# Connector_Board_rev1.net
KiCad netlist of a schematic drawn in EAGLE
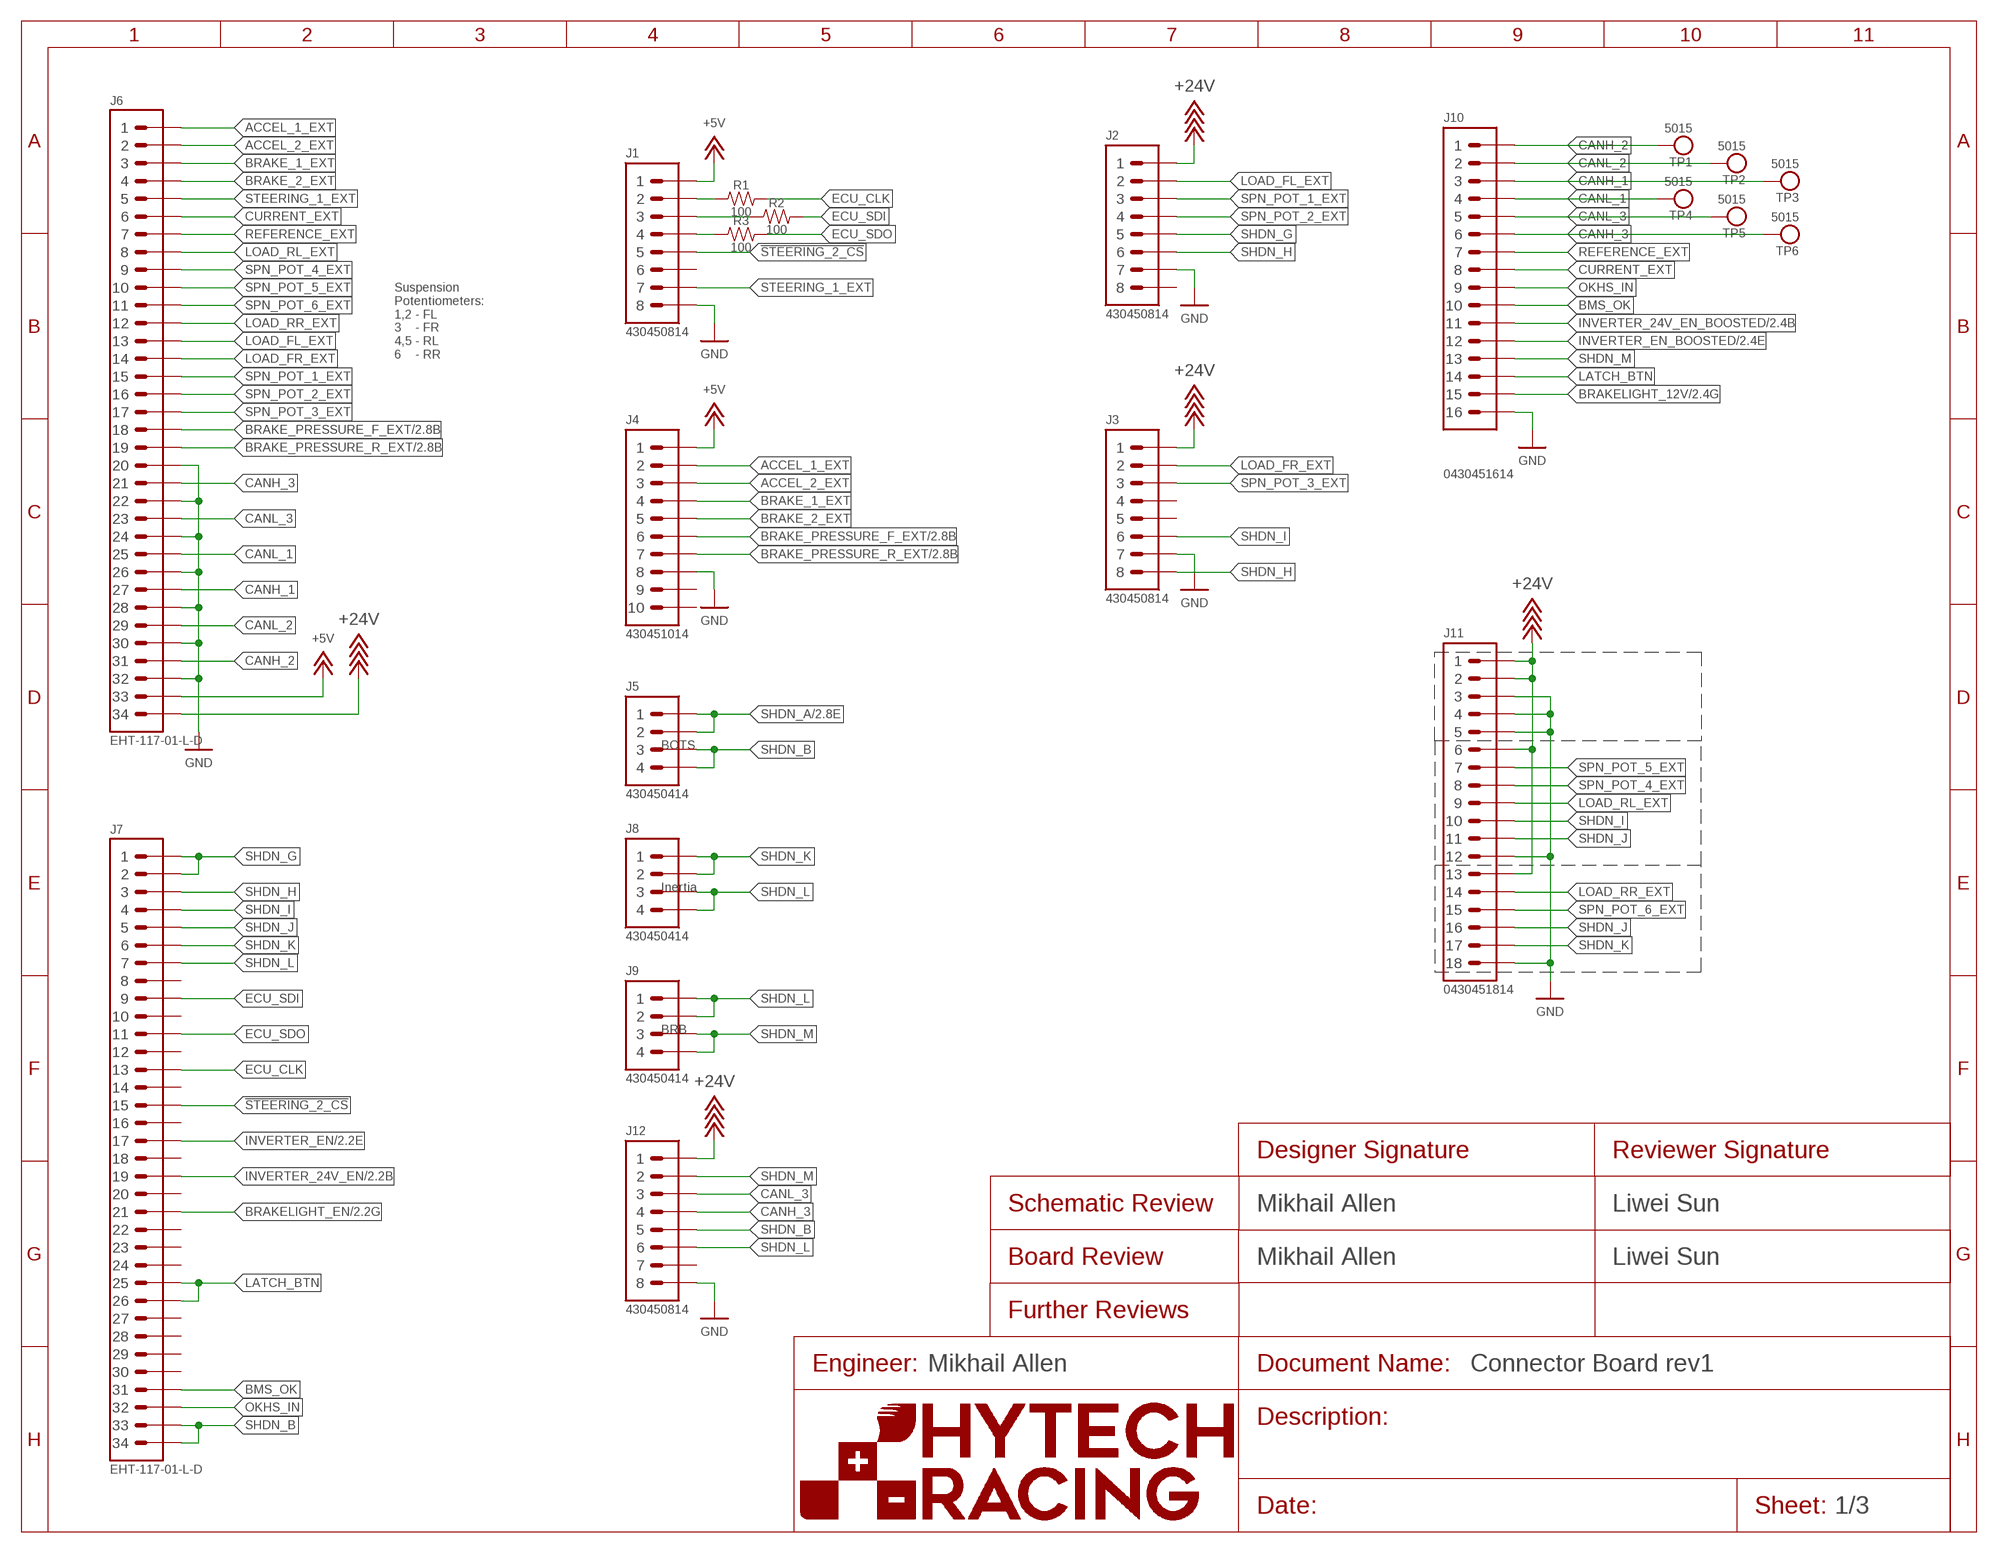
[diagram p0: schematic, sheet 1]
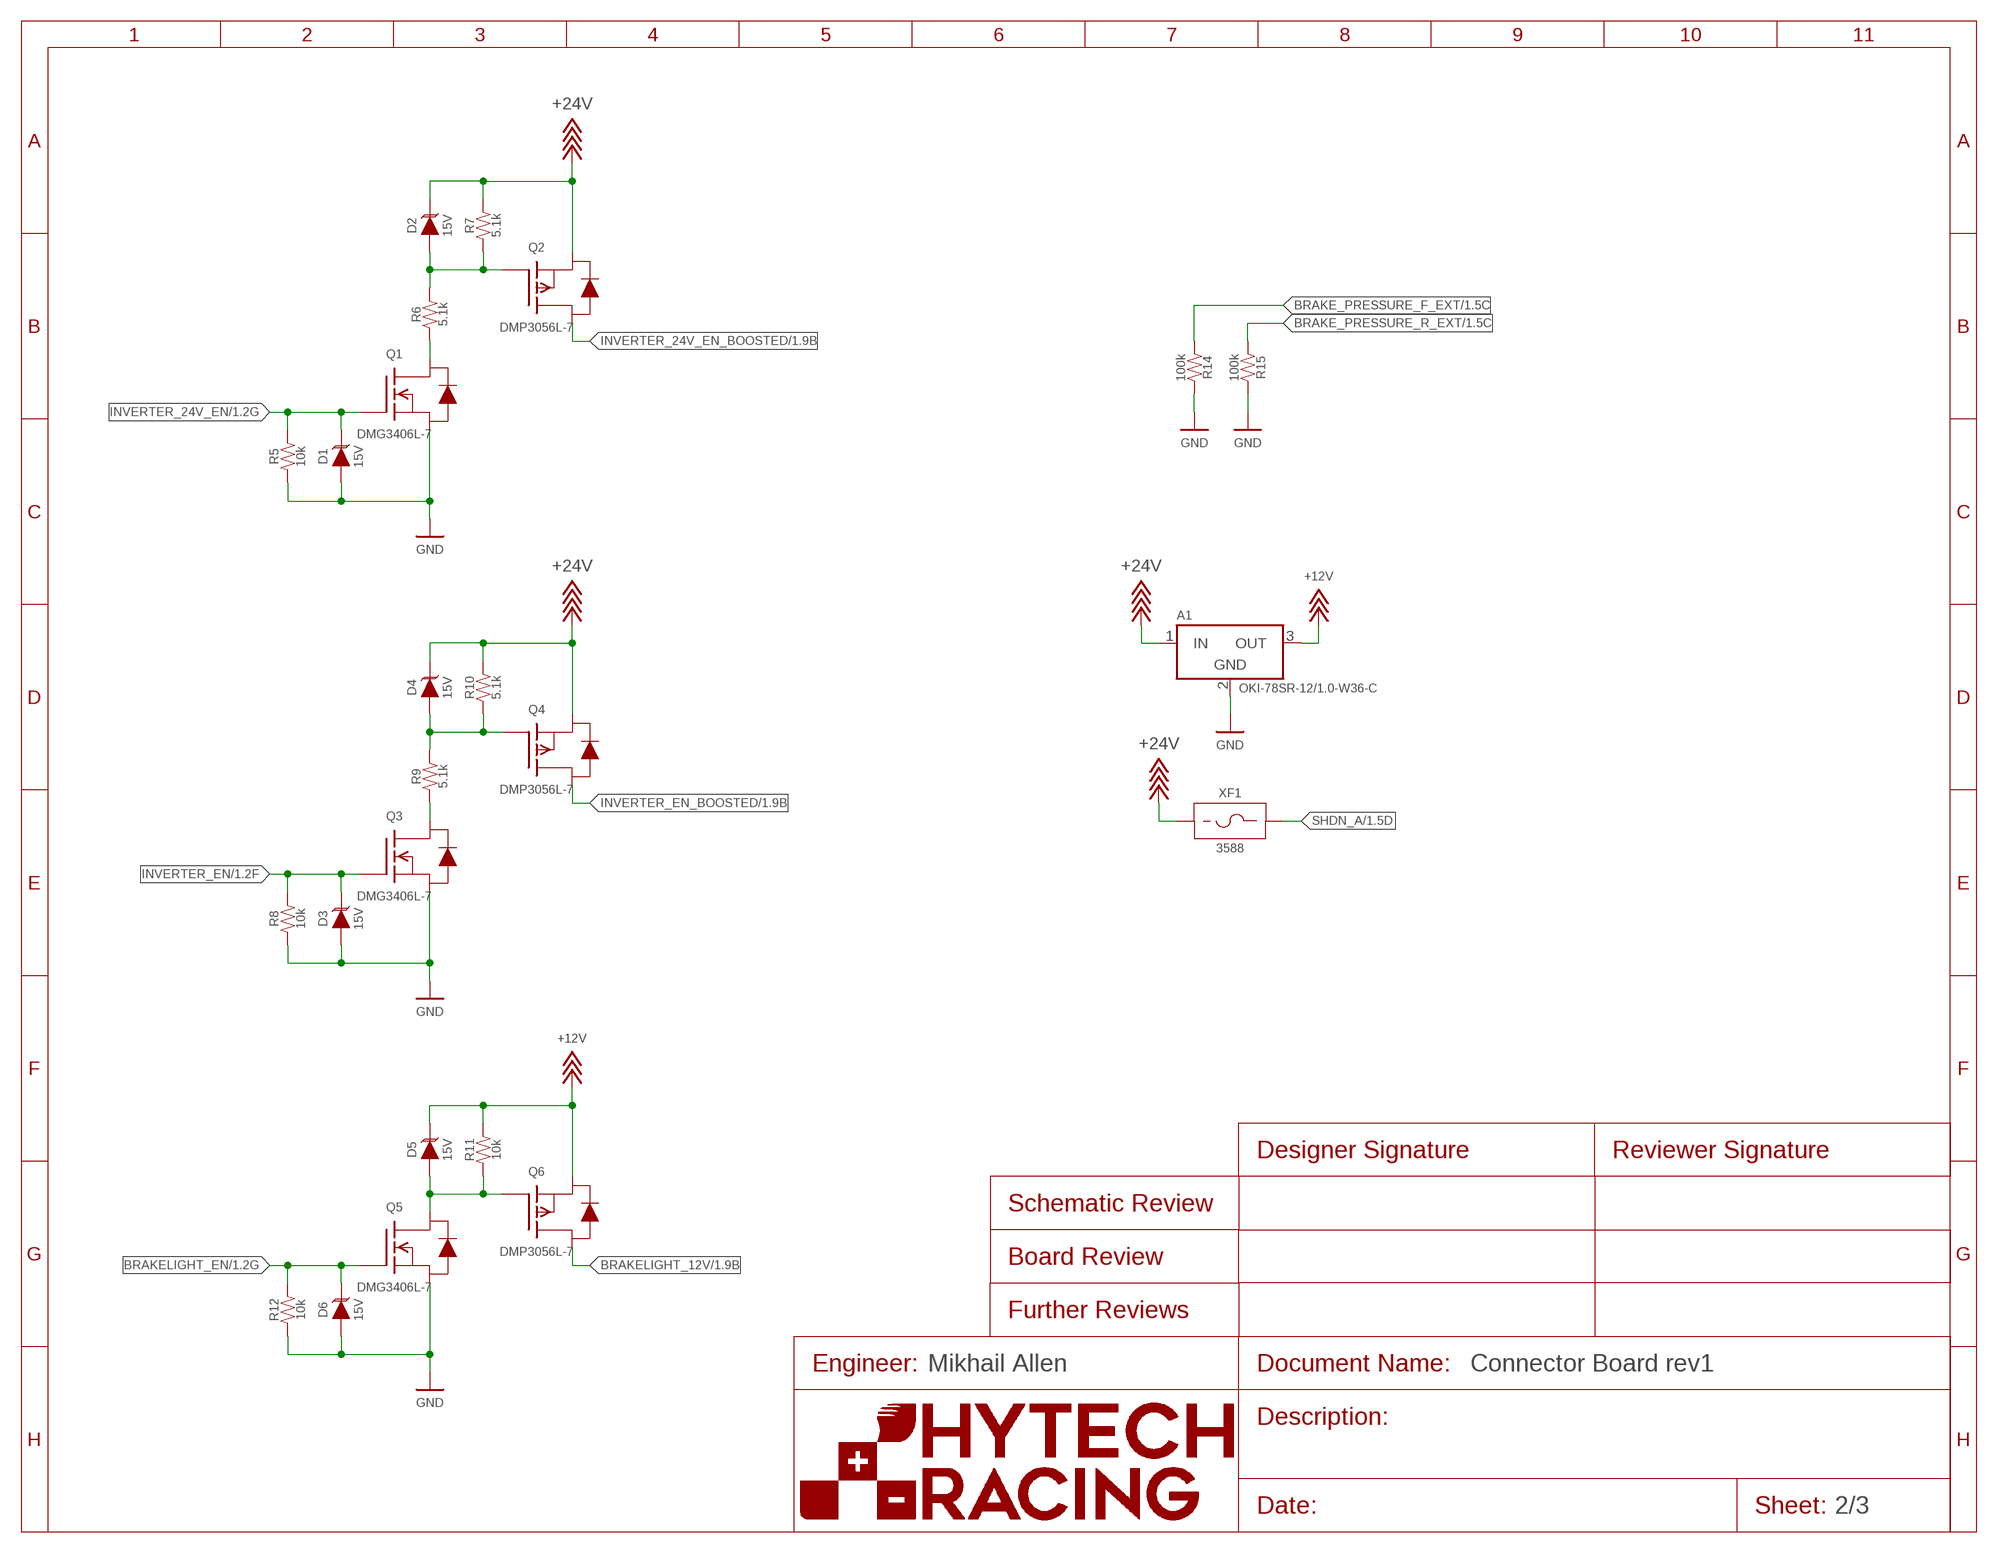
[diagram p1: schematic, sheet 2]
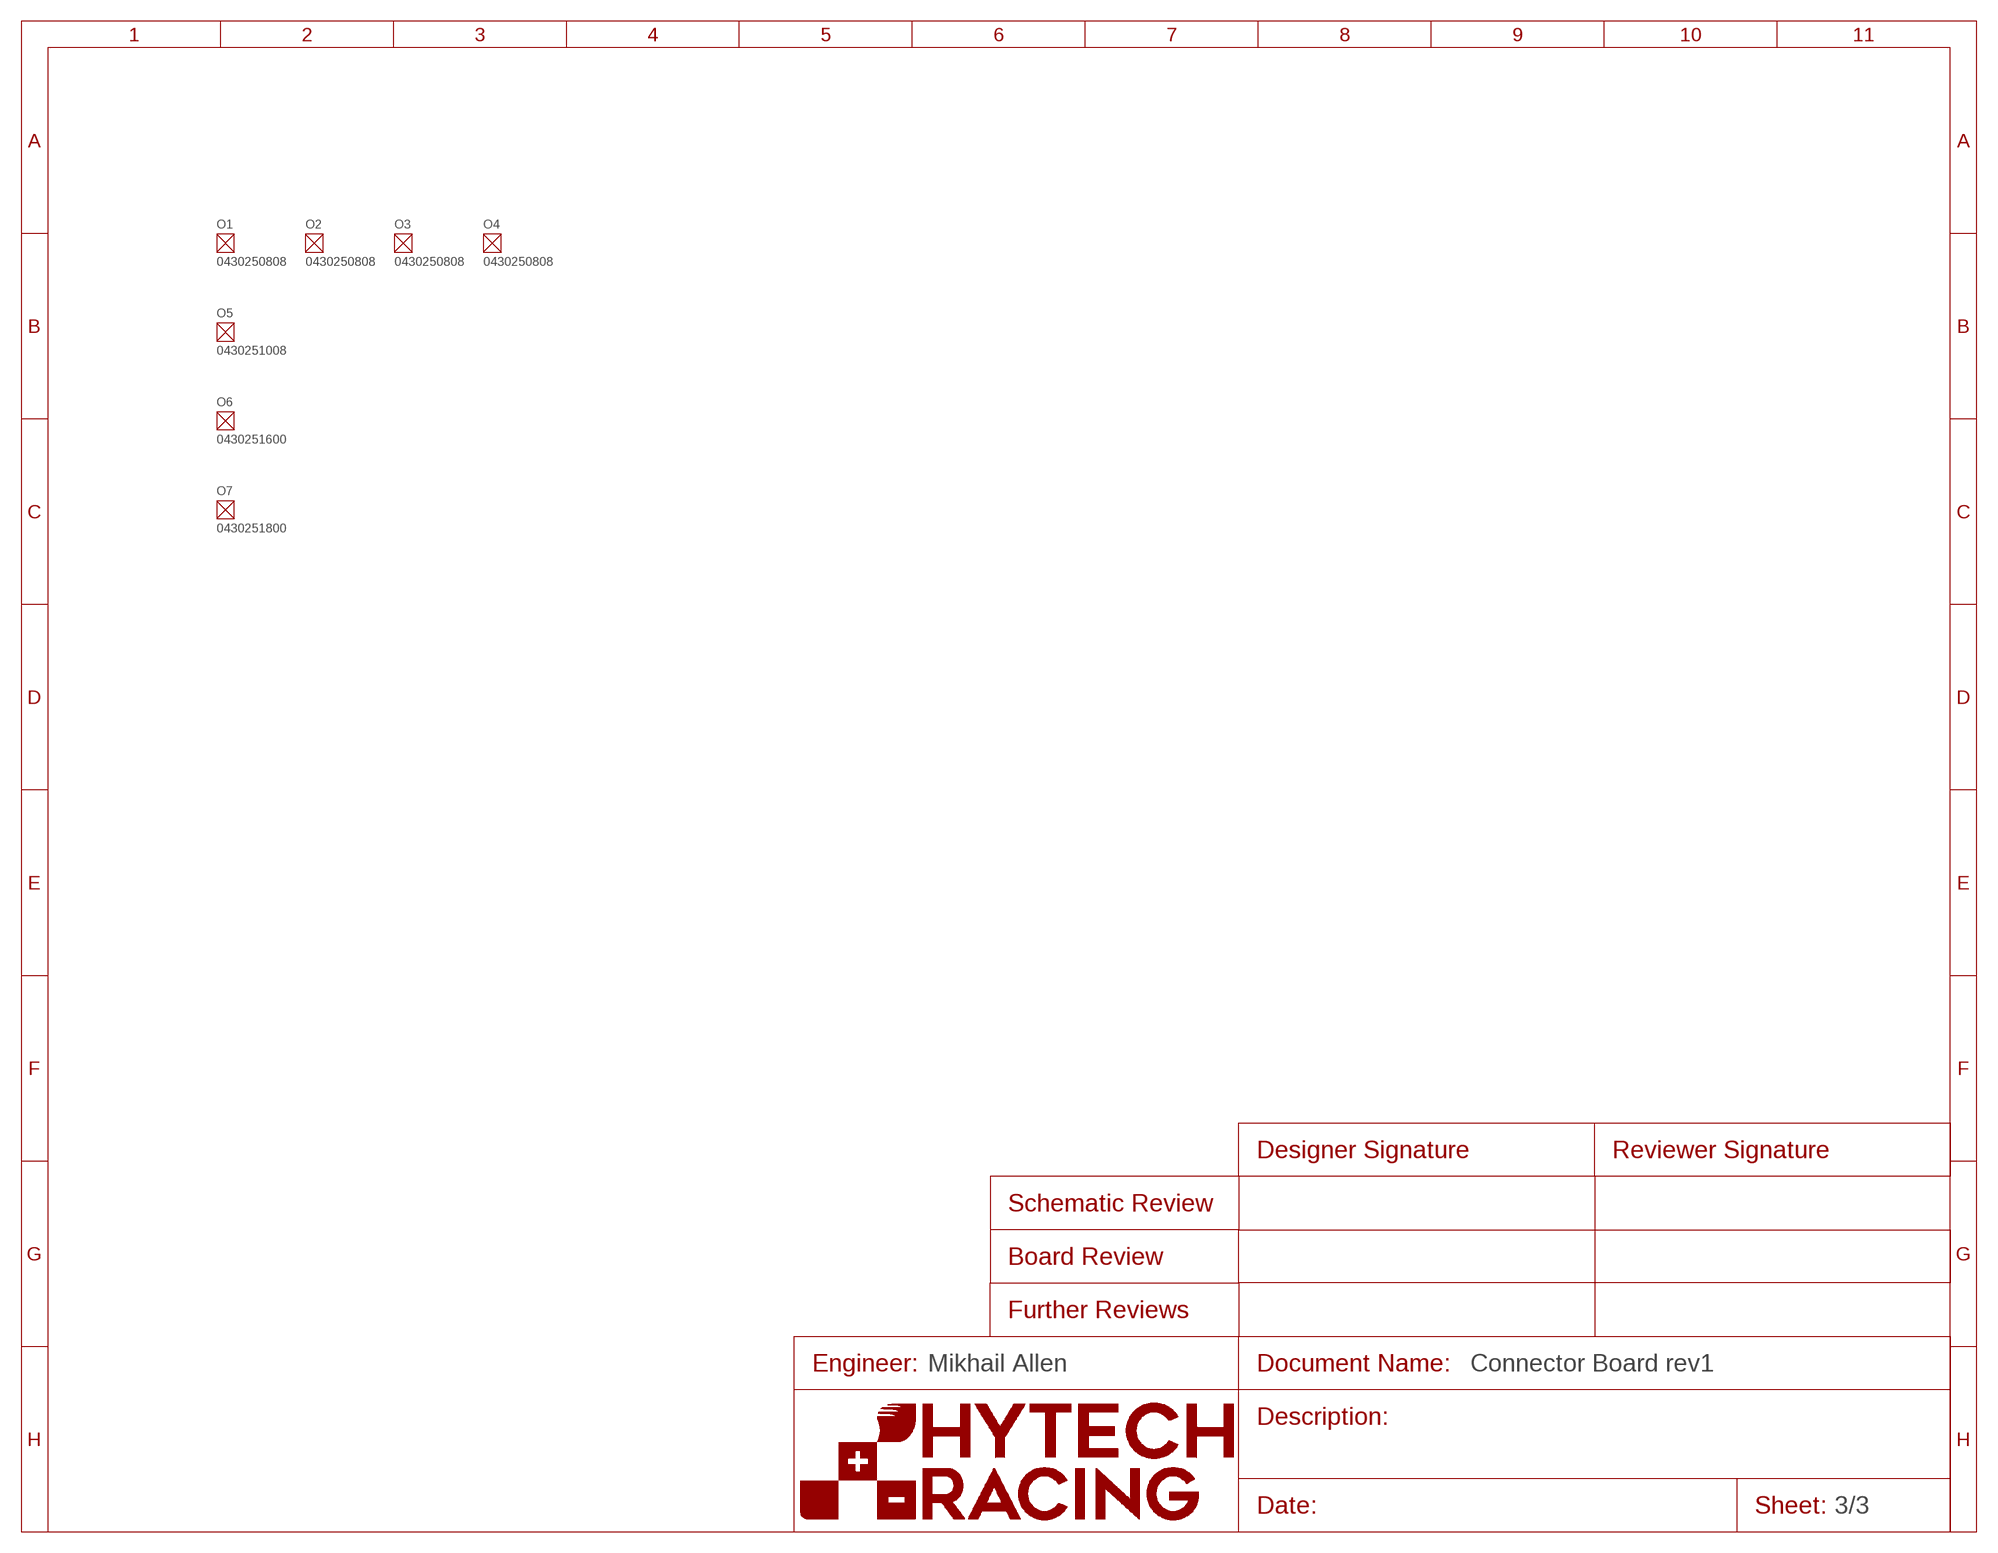
[diagram p2: schematic, sheet 3]

(export (version "E")
  (design (tool "Eeschema 10.0.6"))
  (components
    (comp (ref "A1")
      (value "VOLTAGE_REGULATOR_MODULE_OKI-78SR_12V")
      (footprint "eagle-import:OKI-78SR")
      (fields
        (field (name "MANUFACTURER") "Murata Power Solutions Inc.")
        (field (name "MPN") "OKI-78SR-12/1.0-W36-C")
      )
      (libsource (lib "eagle-import") (part "VOLTAGE_REGULATOR_MODULE_?_OKI-78SR12V"))
    )
    (comp (ref "D1")
      (value "TVS__15V")
      (footprint "eagle-import:SOT-23")
      (fields
        (field (name "MANUFACTURER") "Vishay General Semiconductor - Diodes Division")
        (field (name "MPN") "GSOT15-E3-08")
        (field (name "VOLTAGE") "15V")
      )
      (libsource (lib "eagle-import") (part "TVS_?_15V"))
    )
    (comp (ref "D2")
      (value "TVS__15V")
      (footprint "eagle-import:SOT-23")
      (fields
        (field (name "MANUFACTURER") "Vishay General Semiconductor - Diodes Division")
        (field (name "MPN") "GSOT15-E3-08")
        (field (name "VOLTAGE") "15V")
      )
      (libsource (lib "eagle-import") (part "TVS_?_15V"))
    )
    (comp (ref "D3")
      (value "TVS__15V")
      (footprint "eagle-import:SOT-23")
      (fields
        (field (name "MANUFACTURER") "Vishay General Semiconductor - Diodes Division")
        (field (name "MPN") "GSOT15-E3-08")
        (field (name "VOLTAGE") "15V")
      )
      (libsource (lib "eagle-import") (part "TVS_?_15V"))
    )
    (comp (ref "D4")
      (value "TVS__15V")
      (footprint "eagle-import:SOT-23")
      (fields
        (field (name "MANUFACTURER") "Vishay General Semiconductor - Diodes Division")
        (field (name "MPN") "GSOT15-E3-08")
        (field (name "VOLTAGE") "15V")
      )
      (libsource (lib "eagle-import") (part "TVS_?_15V"))
    )
    (comp (ref "D5")
      (value "TVS__15V")
      (footprint "eagle-import:SOT-23")
      (fields
        (field (name "MANUFACTURER") "Vishay General Semiconductor - Diodes Division")
        (field (name "MPN") "GSOT15-E3-08")
        (field (name "VOLTAGE") "15V")
      )
      (libsource (lib "eagle-import") (part "TVS_?_15V"))
    )
    (comp (ref "D6")
      (value "TVS__15V")
      (footprint "eagle-import:SOT-23")
      (fields
        (field (name "MANUFACTURER") "Vishay General Semiconductor - Diodes Division")
        (field (name "MPN") "GSOT15-E3-08")
        (field (name "VOLTAGE") "15V")
      )
      (libsource (lib "eagle-import") (part "TVS_?_15V"))
    )
    (comp (ref "Q1")
      (value "TRANSISTOR_N_MOS__DMG3406L-7")
      (footprint "eagle-import:SOT-23")
      (fields (field (name "MANUFACTURER") "Diodes Incorporated") (field (name "MPN") "DMG3406L-7"))
      (libsource (lib "eagle-import") (part "TRANSISTOR_N_MOS_?_DMG3406L-7"))
    )
    (comp (ref "Q2")
      (value "TRANSISTOR_P_MOS_SOT-23_DMP3056L-7")
      (footprint "eagle-import:SOT-23")
      (fields (field (name "MANUFACTURER") "Diodes Incorporated") (field (name "MPN") "DMP3056L-7"))
      (libsource (lib "eagle-import") (part "TRANSISTOR_P_MOS_?_SOT-23DMP3056L-7"))
    )
    (comp (ref "Q3")
      (value "TRANSISTOR_N_MOS__DMG3406L-7")
      (footprint "eagle-import:SOT-23")
      (fields (field (name "MANUFACTURER") "Diodes Incorporated") (field (name "MPN") "DMG3406L-7"))
      (libsource (lib "eagle-import") (part "TRANSISTOR_N_MOS_?_DMG3406L-7"))
    )
    (comp (ref "Q4")
      (value "TRANSISTOR_P_MOS_SOT-23_DMP3056L-7")
      (footprint "eagle-import:SOT-23")
      (fields (field (name "MANUFACTURER") "Diodes Incorporated") (field (name "MPN") "DMP3056L-7"))
      (libsource (lib "eagle-import") (part "TRANSISTOR_P_MOS_?_SOT-23DMP3056L-7"))
    )
    (comp (ref "Q5")
      (value "TRANSISTOR_N_MOS__DMG3406L-7")
      (footprint "eagle-import:SOT-23")
      (fields (field (name "MANUFACTURER") "Diodes Incorporated") (field (name "MPN") "DMG3406L-7"))
      (libsource (lib "eagle-import") (part "TRANSISTOR_N_MOS_?_DMG3406L-7"))
    )
    (comp (ref "Q6")
      (value "TRANSISTOR_P_MOS_SOT-23_DMP3056L-7")
      (footprint "eagle-import:SOT-23")
      (fields (field (name "MANUFACTURER") "Diodes Incorporated") (field (name "MPN") "DMP3056L-7"))
      (libsource (lib "eagle-import") (part "TRANSISTOR_P_MOS_?_SOT-23DMP3056L-7"))
    )
    (comp (ref "R5")
      (value "RESISTOR_0603_10K")
      (footprint "eagle-import:0603-RES")
      (fields
        (field (name "MANUFACTURER") "Panasonic Electronic Components")
        (field (name "MPN") "ERA-3ARB103V")
        (field (name "POWER") "0.1W")
        (field (name "RESISTANCE") "10k")
      )
      (libsource (lib "eagle-import") (part "RESISTOR_?_060310K"))
    )
    (comp (ref "R6")
      (value "RESISTOR_0603_5.1K")
      (footprint "eagle-import:0603-RES")
      (fields
        (field (name "MANUFACTURER") "Yageo")
        (field (name "MPN") "RC0603FR-075K1L")
        (field (name "POWER") "0.1W")
        (field (name "RESISTANCE") "5.1k")
      )
      (libsource (lib "eagle-import") (part "RESISTOR_?_06035.1K"))
    )
    (comp (ref "R7")
      (value "RESISTOR_0603_5.1K")
      (footprint "eagle-import:0603-RES")
      (fields
        (field (name "MANUFACTURER") "Yageo")
        (field (name "MPN") "RC0603FR-075K1L")
        (field (name "POWER") "0.1W")
        (field (name "RESISTANCE") "5.1k")
      )
      (libsource (lib "eagle-import") (part "RESISTOR_?_06035.1K"))
    )
    (comp (ref "R8")
      (value "RESISTOR_0603_10K")
      (footprint "eagle-import:0603-RES")
      (fields
        (field (name "MANUFACTURER") "Panasonic Electronic Components")
        (field (name "MPN") "ERA-3ARB103V")
        (field (name "POWER") "0.1W")
        (field (name "RESISTANCE") "10k")
      )
      (libsource (lib "eagle-import") (part "RESISTOR_?_060310K"))
    )
    (comp (ref "R9")
      (value "RESISTOR_0603_5.1K")
      (footprint "eagle-import:0603-RES")
      (fields
        (field (name "MANUFACTURER") "Yageo")
        (field (name "MPN") "RC0603FR-075K1L")
        (field (name "POWER") "0.1W")
        (field (name "RESISTANCE") "5.1k")
      )
      (libsource (lib "eagle-import") (part "RESISTOR_?_06035.1K"))
    )
    (comp (ref "R10")
      (value "RESISTOR_0603_5.1K")
      (footprint "eagle-import:0603-RES")
      (fields
        (field (name "MANUFACTURER") "Yageo")
        (field (name "MPN") "RC0603FR-075K1L")
        (field (name "POWER") "0.1W")
        (field (name "RESISTANCE") "5.1k")
      )
      (libsource (lib "eagle-import") (part "RESISTOR_?_06035.1K"))
    )
    (comp (ref "R11")
      (value "RESISTOR_0603_10K")
      (footprint "eagle-import:0603-RES")
      (fields
        (field (name "MANUFACTURER") "Panasonic Electronic Components")
        (field (name "MPN") "ERA-3ARB103V")
        (field (name "POWER") "0.1W")
        (field (name "RESISTANCE") "10k")
      )
      (libsource (lib "eagle-import") (part "RESISTOR_?_060310K"))
    )
    (comp (ref "R12")
      (value "RESISTOR_0603_10K")
      (footprint "eagle-import:0603-RES")
      (fields
        (field (name "MANUFACTURER") "Panasonic Electronic Components")
        (field (name "MPN") "ERA-3ARB103V")
        (field (name "POWER") "0.1W")
        (field (name "RESISTANCE") "10k")
      )
      (libsource (lib "eagle-import") (part "RESISTOR_?_060310K"))
    )
    (comp (ref "R14")
      (value "RESISTOR_0603_100K")
      (footprint "eagle-import:0603-RES")
      (fields
        (field (name "MANUFACTURER") "Yageo")
        (field (name "MPN") "RC0603FR-07100KL")
        (field (name "POWER") "0.1W")
        (field (name "RESISTANCE") "100k")
      )
      (libsource (lib "eagle-import") (part "RESISTOR_?_0603100K"))
    )
    (comp (ref "R15")
      (value "RESISTOR_0603_100K")
      (footprint "eagle-import:0603-RES")
      (fields
        (field (name "MANUFACTURER") "Yageo")
        (field (name "MPN") "RC0603FR-07100KL")
        (field (name "POWER") "0.1W")
        (field (name "RESISTANCE") "100k")
      )
      (libsource (lib "eagle-import") (part "RESISTOR_?_0603100K"))
    )
    (comp (ref "XF1")
      (value "FUSE_HOLDER_MINIBLADESMD")
      (footprint "eagle-import:3588")
      (fields (field (name "MANUFACTURER") "Keystone Electronics") (field (name "MPN") "3588"))
      (libsource (lib "eagle-import") (part "FUSE_HOLDER_SMDMINIBLADE"))
    )
    (comp (ref "J1")
      (value "CONNECTOR-8_μF_T_V_BLACK")
      (footprint "eagle-import:MOLEX_MICROFIT_PTH_VERTICAL_08_DUAL")
      (fields (field (name "MANUFACTURER") "Molex") (field (name "MPN") "430450814"))
      (libsource (lib "eagle-import") (part "CONNECTOR-8_?_μF_T_VBLACK"))
    )
    (comp (ref "J2")
      (value "CONNECTOR-8_μF_T_V_BLACK")
      (footprint "eagle-import:MOLEX_MICROFIT_PTH_VERTICAL_08_DUAL")
      (fields (field (name "MANUFACTURER") "Molex") (field (name "MPN") "430450814"))
      (libsource (lib "eagle-import") (part "CONNECTOR-8_?_μF_T_VBLACK"))
    )
    (comp (ref "J3")
      (value "CONNECTOR-8_μF_T_V_BLACK")
      (footprint "eagle-import:MOLEX_MICROFIT_PTH_VERTICAL_08_DUAL")
      (fields (field (name "MANUFACTURER") "Molex") (field (name "MPN") "430450814"))
      (libsource (lib "eagle-import") (part "CONNECTOR-8_?_μF_T_VBLACK"))
    )
    (comp (ref "J4")
      (value "CONNECTOR-10_MF_T_V_")
      (footprint "eagle-import:MOLEX_MICROFIT_PTH_VERTICAL_10_DUAL")
      (fields (field (name "MPN") "430451014") (field (name "MANUFACTURER") "MOLEX"))
      (libsource (lib "eagle-import") (part "CONNECTOR-10_?_MF_T_V"))
    )
    (comp (ref "J5")
      (value "CONNECTOR-4_μF_T_V_BLACK")
      (footprint "eagle-import:MOLEX_MICROFIT_PTH_VERTICAL_04_DUAL")
      (fields (field (name "MANUFACTURER") "Molex") (field (name "MPN") "430450414"))
      (libsource (lib "eagle-import") (part "CONNECTOR-4_?_μF_T_VBLACK"))
    )
    (comp (ref "J6")
      (value "CONNECTOR-34__")
      (footprint "eagle-import:EHT-117-01")
      (fields (field (name "MPN") "EHT-117-01-L-D") (field (name "MANUFACTURER") "Samtec"))
      (libsource (lib "eagle-import") (part "CONNECTOR-34_?_"))
    )
    (comp (ref "J7")
      (value "CONNECTOR-34__")
      (footprint "eagle-import:EHT-117-01")
      (fields (field (name "MPN") "EHT-117-01-L-D") (field (name "MANUFACTURER") "Samtec"))
      (libsource (lib "eagle-import") (part "CONNECTOR-34_?_"))
    )
    (comp (ref "J8")
      (value "CONNECTOR-4_μF_T_V_BLACK")
      (footprint "eagle-import:MOLEX_MICROFIT_PTH_VERTICAL_04_DUAL")
      (fields (field (name "MANUFACTURER") "Molex") (field (name "MPN") "430450414"))
      (libsource (lib "eagle-import") (part "CONNECTOR-4_?_μF_T_VBLACK"))
    )
    (comp (ref "J9")
      (value "CONNECTOR-4_μF_T_V_BLACK")
      (footprint "eagle-import:MOLEX_MICROFIT_PTH_VERTICAL_04_DUAL")
      (fields (field (name "MANUFACTURER") "Molex") (field (name "MPN") "430450414"))
      (libsource (lib "eagle-import") (part "CONNECTOR-4_?_μF_T_VBLACK"))
    )
    (comp (ref "J10")
      (value "CONNECTOR-16_MF_T_V_")
      (footprint "eagle-import:MOLEX_MICROFIT_PTH_VERTICAL_16_DUAL")
      (fields (field (name "MPN") "0430451614") (field (name "MANUFACTURER") "MOLEX"))
      (libsource (lib "eagle-import") (part "CONNECTOR-16_?_MF_T_V"))
    )
    (comp (ref "J11")
      (value "CONNECTOR-18_MF_T_V_")
      (footprint "eagle-import:MOLEX_MICROFIT_PTH_VERTICAL_18_DUAL")
      (fields (field (name "MPN") "0430451814") (field (name "MANUFACTURER") "MOLEX"))
      (libsource (lib "eagle-import") (part "CONNECTOR-18_?_MF_T_V"))
    )
    (comp (ref "J12")
      (value "CONNECTOR-8_μF_T_V_BLACK")
      (footprint "eagle-import:MOLEX_MICROFIT_PTH_VERTICAL_08_DUAL")
      (fields (field (name "MANUFACTURER") "Molex") (field (name "MPN") "430450814"))
      (libsource (lib "eagle-import") (part "CONNECTOR-8_?_μF_T_VBLACK"))
    )
    (comp (ref "R1")
      (value "RESISTOR_0603_100")
      (footprint "eagle-import:0603-RES")
      (fields
        (field (name "MANUFACTURER") "Yageo")
        (field (name "MPN") "RC0603FR-07100RL")
        (field (name "POWER") "0.1W")
        (field (name "RESISTANCE") "100")
      )
      (libsource (lib "eagle-import") (part "RESISTOR_?_0603100"))
    )
    (comp (ref "R2")
      (value "RESISTOR_0603_100")
      (footprint "eagle-import:0603-RES")
      (fields
        (field (name "MANUFACTURER") "Yageo")
        (field (name "MPN") "RC0603FR-07100RL")
        (field (name "POWER") "0.1W")
        (field (name "RESISTANCE") "100")
      )
      (libsource (lib "eagle-import") (part "RESISTOR_?_0603100"))
    )
    (comp (ref "R3")
      (value "RESISTOR_0603_100")
      (footprint "eagle-import:0603-RES")
      (fields
        (field (name "MANUFACTURER") "Yageo")
        (field (name "MPN") "RC0603FR-07100RL")
        (field (name "POWER") "0.1W")
        (field (name "RESISTANCE") "100")
      )
      (libsource (lib "eagle-import") (part "RESISTOR_?_0603100"))
    )
    (comp (ref "TP1")
      (value "TEST_POINT")
      (footprint "eagle-import:5015")
      (fields (field (name "MPN") "5015") (field (name "MANUFACTURER") "Keystone Electronics"))
      (libsource (lib "eagle-import") (part "TEST_POINT"))
    )
    (comp (ref "TP2")
      (value "TEST_POINT")
      (footprint "eagle-import:5015")
      (fields (field (name "MPN") "5015") (field (name "MANUFACTURER") "Keystone Electronics"))
      (libsource (lib "eagle-import") (part "TEST_POINT"))
    )
    (comp (ref "TP3")
      (value "TEST_POINT")
      (footprint "eagle-import:5015")
      (fields (field (name "MPN") "5015") (field (name "MANUFACTURER") "Keystone Electronics"))
      (libsource (lib "eagle-import") (part "TEST_POINT"))
    )
    (comp (ref "TP4")
      (value "TEST_POINT")
      (footprint "eagle-import:5015")
      (fields (field (name "MPN") "5015") (field (name "MANUFACTURER") "Keystone Electronics"))
      (libsource (lib "eagle-import") (part "TEST_POINT"))
    )
    (comp (ref "TP5")
      (value "TEST_POINT")
      (footprint "eagle-import:5015")
      (fields (field (name "MPN") "5015") (field (name "MANUFACTURER") "Keystone Electronics"))
      (libsource (lib "eagle-import") (part "TEST_POINT"))
    )
    (comp (ref "TP6")
      (value "TEST_POINT")
      (footprint "eagle-import:5015")
      (fields (field (name "MPN") "5015") (field (name "MANUFACTURER") "Keystone Electronics"))
      (libsource (lib "eagle-import") (part "TEST_POINT"))
    )
  )
  (nets
    (net (code "1") (name "+5V") (class "Default")
      (node (ref "J1") (pin "1") (pinfunction "1_1") (pintype "passive"))
      (node (ref "J4") (pin "1") (pinfunction "1_1") (pintype "passive"))
      (node (ref "J6") (pin "33") (pinfunction "33_33") (pintype "passive"))
    )
    (net (code "2") (name "+12V") (class "Default")
      (node (ref "A1") (pin "3") (pinfunction "OUT_3") (pintype "power_in"))
      (node (ref "D5") (pin "3") (pinfunction "C_3") (pintype "passive"))
      (node (ref "Q6") (pin "2") (pinfunction "S_2") (pintype "passive"))
      (node (ref "R11") (pin "2") (pinfunction "2_2") (pintype "passive"))
    )
    (net (code "3") (name "+24V") (class "Default")
      (node (ref "A1") (pin "1") (pinfunction "IN_1") (pintype "power_in"))
      (node (ref "D2") (pin "3") (pinfunction "C_3") (pintype "passive"))
      (node (ref "D4") (pin "3") (pinfunction "C_3") (pintype "passive"))
      (node (ref "J11") (pin "1") (pinfunction "1_1") (pintype "passive"))
      (node (ref "J11") (pin "13") (pinfunction "13_13") (pintype "passive"))
      (node (ref "J11") (pin "2") (pinfunction "2_2") (pintype "passive"))
      (node (ref "J11") (pin "6") (pinfunction "6_6") (pintype "passive"))
      (node (ref "J12") (pin "1") (pinfunction "1_1") (pintype "passive"))
      (node (ref "J2") (pin "1") (pinfunction "1_1") (pintype "passive"))
      (node (ref "J3") (pin "1") (pinfunction "1_1") (pintype "passive"))
      (node (ref "J6") (pin "34") (pinfunction "34_34") (pintype "passive"))
      (node (ref "Q2") (pin "2") (pinfunction "S_2") (pintype "passive"))
      (node (ref "Q4") (pin "2") (pinfunction "S_2") (pintype "passive"))
      (node (ref "R10") (pin "2") (pinfunction "2_2") (pintype "passive"))
      (node (ref "R7") (pin "2") (pinfunction "2_2") (pintype "passive"))
      (node (ref "XF1") (pin "1") (pinfunction "1_1") (pintype "passive"))
      (node (ref "XF1") (pin "2") (pinfunction "1_2") (pintype "passive"))
    )
    (net (code "4") (name "ACCEL_1_EXT") (class "Default")
      (node (ref "J4") (pin "2") (pinfunction "2_2") (pintype "passive"))
      (node (ref "J6") (pin "1") (pinfunction "1_1") (pintype "passive"))
    )
    (net (code "5") (name "ACCEL_2_EXT") (class "Default")
      (node (ref "J4") (pin "3") (pinfunction "3_3") (pintype "passive"))
      (node (ref "J6") (pin "2") (pinfunction "2_2") (pintype "passive"))
    )
    (net (code "6") (name "BMS_OK") (class "Default")
      (node (ref "J10") (pin "10") (pinfunction "10_10") (pintype "passive"))
      (node (ref "J7") (pin "31") (pinfunction "31_31") (pintype "passive"))
    )
    (net (code "7") (name "BRAKELIGHT_12V") (class "Default")
      (node (ref "J10") (pin "15") (pinfunction "15_15") (pintype "passive"))
      (node (ref "Q6") (pin "3") (pinfunction "D_3") (pintype "passive"))
    )
    (net (code "8") (name "BRAKELIGHT_EN") (class "Default")
      (node (ref "D6") (pin "3") (pinfunction "C_3") (pintype "passive"))
      (node (ref "J7") (pin "21") (pinfunction "21_21") (pintype "passive"))
      (node (ref "Q5") (pin "1") (pinfunction "G_1") (pintype "passive"))
      (node (ref "R12") (pin "2") (pinfunction "2_2") (pintype "passive"))
    )
    (net (code "9") (name "BRAKE_1_EXT") (class "Default")
      (node (ref "J4") (pin "4") (pinfunction "4_4") (pintype "passive"))
      (node (ref "J6") (pin "3") (pinfunction "3_3") (pintype "passive"))
    )
    (net (code "10") (name "BRAKE_2_EXT") (class "Default")
      (node (ref "J4") (pin "5") (pinfunction "5_5") (pintype "passive"))
      (node (ref "J6") (pin "4") (pinfunction "4_4") (pintype "passive"))
    )
    (net (code "11") (name "BRAKE_PRESSURE_F_EXT") (class "Default")
      (node (ref "J4") (pin "6") (pinfunction "6_6") (pintype "passive"))
      (node (ref "J6") (pin "18") (pinfunction "18_18") (pintype "passive"))
      (node (ref "R14") (pin "1") (pinfunction "1_1") (pintype "passive"))
    )
    (net (code "12") (name "BRAKE_PRESSURE_R_EXT") (class "Default")
      (node (ref "J4") (pin "7") (pinfunction "7_7") (pintype "passive"))
      (node (ref "J6") (pin "19") (pinfunction "19_19") (pintype "passive"))
      (node (ref "R15") (pin "1") (pinfunction "1_1") (pintype "passive"))
    )
    (net (code "13") (name "CANH_1") (class "Default")
      (node (ref "J10") (pin "3") (pinfunction "3_3") (pintype "passive"))
      (node (ref "J6") (pin "27") (pinfunction "27_27") (pintype "passive"))
      (node (ref "TP3") (pin "1") (pinfunction "1_1") (pintype "passive"))
    )
    (net (code "14") (name "CANH_2") (class "Default")
      (node (ref "J10") (pin "1") (pinfunction "1_1") (pintype "passive"))
      (node (ref "J6") (pin "31") (pinfunction "31_31") (pintype "passive"))
      (node (ref "TP1") (pin "1") (pinfunction "1_1") (pintype "passive"))
    )
    (net (code "15") (name "CANH_3") (class "Default")
      (node (ref "J10") (pin "6") (pinfunction "6_6") (pintype "passive"))
      (node (ref "J12") (pin "4") (pinfunction "4_4") (pintype "passive"))
      (node (ref "J6") (pin "21") (pinfunction "21_21") (pintype "passive"))
      (node (ref "TP6") (pin "1") (pinfunction "1_1") (pintype "passive"))
    )
    (net (code "16") (name "CANL_1") (class "Default")
      (node (ref "J10") (pin "4") (pinfunction "4_4") (pintype "passive"))
      (node (ref "J6") (pin "25") (pinfunction "25_25") (pintype "passive"))
      (node (ref "TP4") (pin "1") (pinfunction "1_1") (pintype "passive"))
    )
    (net (code "17") (name "CANL_2") (class "Default")
      (node (ref "J10") (pin "2") (pinfunction "2_2") (pintype "passive"))
      (node (ref "J6") (pin "29") (pinfunction "29_29") (pintype "passive"))
      (node (ref "TP2") (pin "1") (pinfunction "1_1") (pintype "passive"))
    )
    (net (code "18") (name "CANL_3") (class "Default")
      (node (ref "J10") (pin "5") (pinfunction "5_5") (pintype "passive"))
      (node (ref "J12") (pin "3") (pinfunction "3_3") (pintype "passive"))
      (node (ref "J6") (pin "23") (pinfunction "23_23") (pintype "passive"))
      (node (ref "TP5") (pin "1") (pinfunction "1_1") (pintype "passive"))
    )
    (net (code "19") (name "CURRENT_EXT") (class "Default")
      (node (ref "J10") (pin "8") (pinfunction "8_8") (pintype "passive"))
      (node (ref "J6") (pin "6") (pinfunction "6_6") (pintype "passive"))
    )
    (net (code "20") (name "ECU_CLK") (class "Default")
      (node (ref "J7") (pin "13") (pinfunction "13_13") (pintype "passive"))
      (node (ref "R1") (pin "2") (pinfunction "2_2") (pintype "passive"))
    )
    (net (code "21") (name "ECU_SDI") (class "Default")
      (node (ref "J7") (pin "9") (pinfunction "9_9") (pintype "passive"))
      (node (ref "R2") (pin "2") (pinfunction "2_2") (pintype "passive"))
    )
    (net (code "22") (name "ECU_SDO") (class "Default")
      (node (ref "J7") (pin "11") (pinfunction "11_11") (pintype "passive"))
      (node (ref "R3") (pin "2") (pinfunction "2_2") (pintype "passive"))
    )
    (net (code "23") (name "GND") (class "Default")
      (node (ref "A1") (pin "2") (pinfunction "GND_2") (pintype "power_in"))
      (node (ref "D1") (pin "1") (pinfunction "A_1") (pintype "passive"))
      (node (ref "D3") (pin "1") (pinfunction "A_1") (pintype "passive"))
      (node (ref "D6") (pin "1") (pinfunction "A_1") (pintype "passive"))
      (node (ref "J1") (pin "8") (pinfunction "8_8") (pintype "passive"))
      (node (ref "J10") (pin "16") (pinfunction "16_16") (pintype "passive"))
      (node (ref "J11") (pin "12") (pinfunction "12_12") (pintype "passive"))
      (node (ref "J11") (pin "18") (pinfunction "18_18") (pintype "passive"))
      (node (ref "J11") (pin "3") (pinfunction "3_3") (pintype "passive"))
      (node (ref "J11") (pin "4") (pinfunction "4_4") (pintype "passive"))
      (node (ref "J11") (pin "5") (pinfunction "5_5") (pintype "passive"))
      (node (ref "J12") (pin "8") (pinfunction "8_8") (pintype "passive"))
      (node (ref "J2") (pin "7") (pinfunction "7_7") (pintype "passive"))
      (node (ref "J3") (pin "7") (pinfunction "7_7") (pintype "passive"))
      (node (ref "J4") (pin "8") (pinfunction "8_8") (pintype "passive"))
      (node (ref "J6") (pin "20") (pinfunction "20_20") (pintype "passive"))
      (node (ref "J6") (pin "22") (pinfunction "22_22") (pintype "passive"))
      (node (ref "J6") (pin "24") (pinfunction "24_24") (pintype "passive"))
      (node (ref "J6") (pin "26") (pinfunction "26_26") (pintype "passive"))
      (node (ref "J6") (pin "28") (pinfunction "28_28") (pintype "passive"))
      (node (ref "J6") (pin "30") (pinfunction "30_30") (pintype "passive"))
      (node (ref "J6") (pin "32") (pinfunction "32_32") (pintype "passive"))
      (node (ref "Q1") (pin "2") (pinfunction "S_2") (pintype "passive"))
      (node (ref "Q3") (pin "2") (pinfunction "S_2") (pintype "passive"))
      (node (ref "Q5") (pin "2") (pinfunction "S_2") (pintype "passive"))
      (node (ref "R12") (pin "1") (pinfunction "1_1") (pintype "passive"))
      (node (ref "R14") (pin "2") (pinfunction "2_2") (pintype "passive"))
      (node (ref "R15") (pin "2") (pinfunction "2_2") (pintype "passive"))
      (node (ref "R5") (pin "1") (pinfunction "1_1") (pintype "passive"))
      (node (ref "R8") (pin "1") (pinfunction "1_1") (pintype "passive"))
    )
    (net (code "24") (name "INVERTER_24V_EN") (class "Default")
      (node (ref "D1") (pin "3") (pinfunction "C_3") (pintype "passive"))
      (node (ref "J7") (pin "19") (pinfunction "19_19") (pintype "passive"))
      (node (ref "Q1") (pin "1") (pinfunction "G_1") (pintype "passive"))
      (node (ref "R5") (pin "2") (pinfunction "2_2") (pintype "passive"))
    )
    (net (code "25") (name "INVERTER_24V_EN_BOOSTED") (class "Default")
      (node (ref "J10") (pin "11") (pinfunction "11_11") (pintype "passive"))
      (node (ref "Q2") (pin "3") (pinfunction "D_3") (pintype "passive"))
    )
    (net (code "26") (name "INVERTER_EN") (class "Default")
      (node (ref "D3") (pin "3") (pinfunction "C_3") (pintype "passive"))
      (node (ref "J7") (pin "17") (pinfunction "17_17") (pintype "passive"))
      (node (ref "Q3") (pin "1") (pinfunction "G_1") (pintype "passive"))
      (node (ref "R8") (pin "2") (pinfunction "2_2") (pintype "passive"))
    )
    (net (code "27") (name "INVERTER_EN_BOOSTED") (class "Default")
      (node (ref "J10") (pin "12") (pinfunction "12_12") (pintype "passive"))
      (node (ref "Q4") (pin "3") (pinfunction "D_3") (pintype "passive"))
    )
    (net (code "28") (name "LATCH_BTN") (class "Default")
      (node (ref "J10") (pin "14") (pinfunction "14_14") (pintype "passive"))
      (node (ref "J7") (pin "25") (pinfunction "25_25") (pintype "passive"))
      (node (ref "J7") (pin "26") (pinfunction "26_26") (pintype "passive"))
    )
    (net (code "29") (name "LOAD_FL_EXT") (class "Default")
      (node (ref "J2") (pin "2") (pinfunction "2_2") (pintype "passive"))
      (node (ref "J6") (pin "13") (pinfunction "13_13") (pintype "passive"))
    )
    (net (code "30") (name "LOAD_FR_EXT") (class "Default")
      (node (ref "J3") (pin "2") (pinfunction "2_2") (pintype "passive"))
      (node (ref "J6") (pin "14") (pinfunction "14_14") (pintype "passive"))
    )
    (net (code "31") (name "LOAD_RL_EXT") (class "Default")
      (node (ref "J11") (pin "9") (pinfunction "9_9") (pintype "passive"))
      (node (ref "J6") (pin "8") (pinfunction "8_8") (pintype "passive"))
    )
    (net (code "32") (name "LOAD_RR_EXT") (class "Default")
      (node (ref "J11") (pin "14") (pinfunction "14_14") (pintype "passive"))
      (node (ref "J6") (pin "12") (pinfunction "12_12") (pintype "passive"))
    )
    (net (code "33") (name "Net-(D2-A)") (class "Default")
      (node (ref "D2") (pin "1") (pinfunction "A_1") (pintype "passive"))
      (node (ref "Q2") (pin "1") (pinfunction "G_1") (pintype "passive"))
      (node (ref "R6") (pin "2") (pinfunction "2_2") (pintype "passive"))
      (node (ref "R7") (pin "1") (pinfunction "1_1") (pintype "passive"))
    )
    (net (code "34") (name "Net-(D4-A)") (class "Default")
      (node (ref "D4") (pin "1") (pinfunction "A_1") (pintype "passive"))
      (node (ref "Q4") (pin "1") (pinfunction "G_1") (pintype "passive"))
      (node (ref "R10") (pin "1") (pinfunction "1_1") (pintype "passive"))
      (node (ref "R9") (pin "2") (pinfunction "2_2") (pintype "passive"))
    )
    (net (code "35") (name "Net-(D5-A)") (class "Default")
      (node (ref "D5") (pin "1") (pinfunction "A_1") (pintype "passive"))
      (node (ref "Q5") (pin "3") (pinfunction "D_3") (pintype "passive"))
      (node (ref "Q6") (pin "1") (pinfunction "G_1") (pintype "passive"))
      (node (ref "R11") (pin "1") (pinfunction "1_1") (pintype "passive"))
    )
    (net (code "36") (name "Net-(J1-Pad2)") (class "Default")
      (node (ref "J1") (pin "2") (pinfunction "2_2") (pintype "passive"))
      (node (ref "R1") (pin "1") (pinfunction "1_1") (pintype "passive"))
    )
    (net (code "37") (name "Net-(J1-Pad3)") (class "Default")
      (node (ref "J1") (pin "3") (pinfunction "3_3") (pintype "passive"))
      (node (ref "R2") (pin "1") (pinfunction "1_1") (pintype "passive"))
    )
    (net (code "38") (name "Net-(J1-Pad4)") (class "Default")
      (node (ref "J1") (pin "4") (pinfunction "4_4") (pintype "passive"))
      (node (ref "R3") (pin "1") (pinfunction "1_1") (pintype "passive"))
    )
    (net (code "39") (name "Net-(Q1-D)") (class "Default")
      (node (ref "Q1") (pin "3") (pinfunction "D_3") (pintype "passive"))
      (node (ref "R6") (pin "1") (pinfunction "1_1") (pintype "passive"))
    )
    (net (code "40") (name "Net-(Q3-D)") (class "Default")
      (node (ref "Q3") (pin "3") (pinfunction "D_3") (pintype "passive"))
      (node (ref "R9") (pin "1") (pinfunction "1_1") (pintype "passive"))
    )
    (net (code "41") (name "OKHS_IN") (class "Default")
      (node (ref "J10") (pin "9") (pinfunction "9_9") (pintype "passive"))
      (node (ref "J7") (pin "32") (pinfunction "32_32") (pintype "passive"))
    )
    (net (code "42") (name "REFERENCE_EXT") (class "Default")
      (node (ref "J10") (pin "7") (pinfunction "7_7") (pintype "passive"))
      (node (ref "J6") (pin "7") (pinfunction "7_7") (pintype "passive"))
    )
    (net (code "43") (name "SHDN_A") (class "Default")
      (node (ref "J5") (pin "1") (pinfunction "1_1") (pintype "passive"))
      (node (ref "J5") (pin "2") (pinfunction "2_2") (pintype "passive"))
      (node (ref "XF1") (pin "3") (pinfunction "2_3") (pintype "passive"))
      (node (ref "XF1") (pin "4") (pinfunction "2_4") (pintype "passive"))
    )
    (net (code "44") (name "SHDN_B") (class "Default")
      (node (ref "J12") (pin "5") (pinfunction "5_5") (pintype "passive"))
      (node (ref "J5") (pin "3") (pinfunction "3_3") (pintype "passive"))
      (node (ref "J5") (pin "4") (pinfunction "4_4") (pintype "passive"))
      (node (ref "J7") (pin "33") (pinfunction "33_33") (pintype "passive"))
      (node (ref "J7") (pin "34") (pinfunction "34_34") (pintype "passive"))
    )
    (net (code "45") (name "SHDN_G") (class "Default")
      (node (ref "J2") (pin "5") (pinfunction "5_5") (pintype "passive"))
      (node (ref "J7") (pin "1") (pinfunction "1_1") (pintype "passive"))
      (node (ref "J7") (pin "2") (pinfunction "2_2") (pintype "passive"))
    )
    (net (code "46") (name "SHDN_H") (class "Default")
      (node (ref "J2") (pin "6") (pinfunction "6_6") (pintype "passive"))
      (node (ref "J3") (pin "8") (pinfunction "8_8") (pintype "passive"))
      (node (ref "J7") (pin "3") (pinfunction "3_3") (pintype "passive"))
    )
    (net (code "47") (name "SHDN_I") (class "Default")
      (node (ref "J11") (pin "10") (pinfunction "10_10") (pintype "passive"))
      (node (ref "J3") (pin "6") (pinfunction "6_6") (pintype "passive"))
      (node (ref "J7") (pin "4") (pinfunction "4_4") (pintype "passive"))
    )
    (net (code "48") (name "SHDN_J") (class "Default")
      (node (ref "J11") (pin "11") (pinfunction "11_11") (pintype "passive"))
      (node (ref "J11") (pin "16") (pinfunction "16_16") (pintype "passive"))
      (node (ref "J7") (pin "5") (pinfunction "5_5") (pintype "passive"))
    )
    (net (code "49") (name "SHDN_K") (class "Default")
      (node (ref "J11") (pin "17") (pinfunction "17_17") (pintype "passive"))
      (node (ref "J7") (pin "6") (pinfunction "6_6") (pintype "passive"))
      (node (ref "J8") (pin "1") (pinfunction "1_1") (pintype "passive"))
      (node (ref "J8") (pin "2") (pinfunction "2_2") (pintype "passive"))
    )
    (net (code "50") (name "SHDN_L") (class "Default")
      (node (ref "J12") (pin "6") (pinfunction "6_6") (pintype "passive"))
      (node (ref "J7") (pin "7") (pinfunction "7_7") (pintype "passive"))
      (node (ref "J8") (pin "3") (pinfunction "3_3") (pintype "passive"))
      (node (ref "J8") (pin "4") (pinfunction "4_4") (pintype "passive"))
      (node (ref "J9") (pin "1") (pinfunction "1_1") (pintype "passive"))
      (node (ref "J9") (pin "2") (pinfunction "2_2") (pintype "passive"))
    )
    (net (code "51") (name "SHDN_M") (class "Default")
      (node (ref "J10") (pin "13") (pinfunction "13_13") (pintype "passive"))
      (node (ref "J12") (pin "2") (pinfunction "2_2") (pintype "passive"))
      (node (ref "J9") (pin "3") (pinfunction "3_3") (pintype "passive"))
      (node (ref "J9") (pin "4") (pinfunction "4_4") (pintype "passive"))
    )
    (net (code "52") (name "SPN_POT_1_EXT") (class "Default")
      (node (ref "J2") (pin "3") (pinfunction "3_3") (pintype "passive"))
      (node (ref "J6") (pin "15") (pinfunction "15_15") (pintype "passive"))
    )
    (net (code "53") (name "SPN_POT_2_EXT") (class "Default")
      (node (ref "J2") (pin "4") (pinfunction "4_4") (pintype "passive"))
      (node (ref "J6") (pin "16") (pinfunction "16_16") (pintype "passive"))
    )
    (net (code "54") (name "SPN_POT_3_EXT") (class "Default")
      (node (ref "J3") (pin "3") (pinfunction "3_3") (pintype "passive"))
      (node (ref "J6") (pin "17") (pinfunction "17_17") (pintype "passive"))
    )
    (net (code "55") (name "SPN_POT_4_EXT") (class "Default")
      (node (ref "J11") (pin "8") (pinfunction "8_8") (pintype "passive"))
      (node (ref "J6") (pin "9") (pinfunction "9_9") (pintype "passive"))
    )
    (net (code "56") (name "SPN_POT_5_EXT") (class "Default")
      (node (ref "J11") (pin "7") (pinfunction "7_7") (pintype "passive"))
      (node (ref "J6") (pin "10") (pinfunction "10_10") (pintype "passive"))
    )
    (net (code "57") (name "SPN_POT_6_EXT") (class "Default")
      (node (ref "J11") (pin "15") (pinfunction "15_15") (pintype "passive"))
      (node (ref "J6") (pin "11") (pinfunction "11_11") (pintype "passive"))
    )
    (net (code "58") (name "STEERING_1_EXT") (class "Default")
      (node (ref "J1") (pin "7") (pinfunction "7_7") (pintype "passive"))
      (node (ref "J6") (pin "5") (pinfunction "5_5") (pintype "passive"))
    )
    (net (code "59") (name "unconnected-(J1-Pad6)") (class "Default")
      (node (ref "J1") (pin "6") (pinfunction "6_6") (pintype "passive"))
    )
    (net (code "60") (name "unconnected-(J2-Pad8)") (class "Default")
      (node (ref "J2") (pin "8") (pinfunction "8_8") (pintype "passive"))
    )
    (net (code "61") (name "unconnected-(J3-Pad4)") (class "Default")
      (node (ref "J3") (pin "4") (pinfunction "4_4") (pintype "passive"))
    )
    (net (code "62") (name "unconnected-(J3-Pad5)") (class "Default")
      (node (ref "J3") (pin "5") (pinfunction "5_5") (pintype "passive"))
    )
    (net (code "63") (name "unconnected-(J4-Pad9)") (class "Default")
      (node (ref "J4") (pin "9") (pinfunction "9_9") (pintype "passive"))
    )
    (net (code "64") (name "unconnected-(J4-Pad10)") (class "Default")
      (node (ref "J4") (pin "10") (pinfunction "10_10") (pintype "passive"))
    )
    (net (code "65") (name "unconnected-(J7-Pad8)") (class "Default")
      (node (ref "J7") (pin "8") (pinfunction "8_8") (pintype "passive"))
    )
    (net (code "66") (name "unconnected-(J7-Pad10)") (class "Default")
      (node (ref "J7") (pin "10") (pinfunction "10_10") (pintype "passive"))
    )
    (net (code "67") (name "unconnected-(J7-Pad12)") (class "Default")
      (node (ref "J7") (pin "12") (pinfunction "12_12") (pintype "passive"))
    )
    (net (code "68") (name "unconnected-(J7-Pad14)") (class "Default")
      (node (ref "J7") (pin "14") (pinfunction "14_14") (pintype "passive"))
    )
    (net (code "69") (name "unconnected-(J7-Pad16)") (class "Default")
      (node (ref "J7") (pin "16") (pinfunction "16_16") (pintype "passive"))
    )
    (net (code "70") (name "unconnected-(J7-Pad18)") (class "Default")
      (node (ref "J7") (pin "18") (pinfunction "18_18") (pintype "passive"))
    )
    (net (code "71") (name "unconnected-(J7-Pad20)") (class "Default")
      (node (ref "J7") (pin "20") (pinfunction "20_20") (pintype "passive"))
    )
    (net (code "72") (name "unconnected-(J7-Pad22)") (class "Default")
      (node (ref "J7") (pin "22") (pinfunction "22_22") (pintype "passive"))
    )
    (net (code "73") (name "unconnected-(J7-Pad23)") (class "Default")
      (node (ref "J7") (pin "23") (pinfunction "23_23") (pintype "passive"))
    )
    (net (code "74") (name "unconnected-(J7-Pad24)") (class "Default")
      (node (ref "J7") (pin "24") (pinfunction "24_24") (pintype "passive"))
    )
    (net (code "75") (name "unconnected-(J7-Pad27)") (class "Default")
      (node (ref "J7") (pin "27") (pinfunction "27_27") (pintype "passive"))
    )
    (net (code "76") (name "unconnected-(J7-Pad28)") (class "Default")
      (node (ref "J7") (pin "28") (pinfunction "28_28") (pintype "passive"))
    )
    (net (code "77") (name "unconnected-(J7-Pad29)") (class "Default")
      (node (ref "J7") (pin "29") (pinfunction "29_29") (pintype "passive"))
    )
    (net (code "78") (name "unconnected-(J7-Pad30)") (class "Default")
      (node (ref "J7") (pin "30") (pinfunction "30_30") (pintype "passive"))
    )
    (net (code "79") (name "unconnected-(J12-Pad7)") (class "Default")
      (node (ref "J12") (pin "7") (pinfunction "7_7") (pintype "passive"))
    )
    (net (code "80") (name "~{STEERING_2_CS}") (class "Default")
      (node (ref "J1") (pin "5") (pinfunction "5_5") (pintype "passive"))
      (node (ref "J7") (pin "15") (pinfunction "15_15") (pintype "passive"))
    )
  )
)
